# Cover.net
KiCad netlist of a schematic drawn in EAGLE
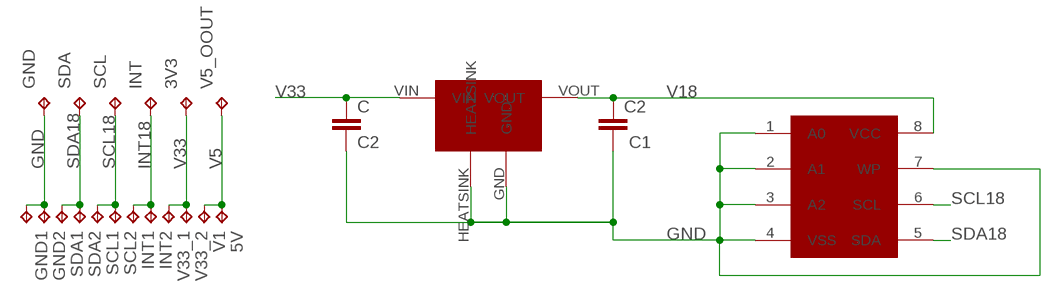
[diagram p0: schematic, sheet 1]

(export (version "E")
  (design (tool "Eeschema 10.0.6"))
  (components
    (comp (ref "3V3")
      (value "TPTP20SQ")
      (footprint "eagle-import:TP20SQ")
      (libsource (lib "eagle-import") (part "TPTP20SQ"))
    )
    (comp (ref "5V")
      (value "V5")
      (footprint "eagle-import:TP20SQ")
      (libsource (lib "eagle-import") (part "TPTP20SQ"))
    )
    (comp (ref "C")
      (value "C2")
      (footprint "eagle-import:C0603")
      (libsource (lib "eagle-import") (part "C-EUC0603"))
    )
    (comp (ref "C2")
      (value "C1")
      (footprint "eagle-import:C0603")
      (libsource (lib "eagle-import") (part "C-EUC0603"))
    )
    (comp (ref "GND")
      (value "TPTP20SQ")
      (footprint "eagle-import:TP20SQ")
      (libsource (lib "eagle-import") (part "TPTP20SQ"))
    )
    (comp (ref "GND1")
      (value "TPTP20SQ")
      (footprint "eagle-import:TP20SQ")
      (libsource (lib "eagle-import") (part "TPTP20SQ"))
    )
    (comp (ref "GND2")
      (value "TPTP20SQ")
      (footprint "eagle-import:TP20SQ")
      (libsource (lib "eagle-import") (part "TPTP20SQ"))
    )
    (comp (ref "INT")
      (value "TPTP20SQ")
      (footprint "eagle-import:TP20SQ")
      (libsource (lib "eagle-import") (part "TPTP20SQ"))
    )
    (comp (ref "INT1")
      (value "TPTP20SQ")
      (footprint "eagle-import:TP20SQ")
      (libsource (lib "eagle-import") (part "TPTP20SQ"))
    )
    (comp (ref "INT2")
      (value "TPTP20SQ")
      (footprint "eagle-import:TP20SQ")
      (libsource (lib "eagle-import") (part "TPTP20SQ"))
    )
    (comp (ref "SCL")
      (value "TPTP20SQ")
      (footprint "eagle-import:TP20SQ")
      (libsource (lib "eagle-import") (part "TPTP20SQ"))
    )
    (comp (ref "SCL1")
      (value "TPTP20SQ")
      (footprint "eagle-import:TP20SQ")
      (libsource (lib "eagle-import") (part "TPTP20SQ"))
    )
    (comp (ref "SCL2")
      (value "TPTP20SQ")
      (footprint "eagle-import:TP20SQ")
      (libsource (lib "eagle-import") (part "TPTP20SQ"))
    )
    (comp (ref "SDA")
      (value "TPTP20SQ")
      (footprint "eagle-import:TP20SQ")
      (libsource (lib "eagle-import") (part "TPTP20SQ"))
    )
    (comp (ref "SDA1")
      (value "SDA")
      (footprint "eagle-import:TP20SQ")
      (libsource (lib "eagle-import") (part "TPTP20SQ"))
    )
    (comp (ref "SDA2")
      (value "SDA")
      (footprint "eagle-import:TP20SQ")
      (libsource (lib "eagle-import") (part "TPTP20SQ"))
    )
    (comp (ref "U$1")
      (value "CAT24")
      (footprint "eagle-import:CAT24")
      (libsource (lib "eagle-import") (part "CAT24"))
    )
    (comp (ref "U$2")
      (value "MCP1700-DFN6")
      (footprint "eagle-import:DFN6-2X2")
      (libsource (lib "eagle-import") (part "MCP1700-DFN6"))
    )
    (comp (ref "V1")
      (value "V5")
      (footprint "eagle-import:TP20SQ")
      (libsource (lib "eagle-import") (part "TPTP20SQ"))
    )
    (comp (ref "V5_OOUT")
      (value "TPTP20SQ")
      (footprint "eagle-import:TP20SQ")
      (libsource (lib "eagle-import") (part "TPTP20SQ"))
    )
    (comp (ref "V33_1")
      (value "TPTP20SQ")
      (footprint "eagle-import:TP20SQ")
      (libsource (lib "eagle-import") (part "TPTP20SQ"))
    )
    (comp (ref "V33_2")
      (value "TPTP20SQ")
      (footprint "eagle-import:TP20SQ")
      (libsource (lib "eagle-import") (part "TPTP20SQ"))
    )
  )
  (nets
    (net (code "1") (name "/GND") (class "Default")
      (node (ref "C") (pin "2") (pinfunction "2_2") (pintype "passive"))
      (node (ref "C2") (pin "2") (pinfunction "2_2") (pintype "passive"))
      (node (ref "GND") (pin "TP") (pinfunction "TP_TP") (pintype "input"))
      (node (ref "GND1") (pin "TP") (pinfunction "TP_TP") (pintype "input"))
      (node (ref "GND2") (pin "TP") (pinfunction "TP_TP") (pintype "input"))
      (node (ref "U$1") (pin "1") (pinfunction "A0_1") (pintype "bidirectional"))
      (node (ref "U$1") (pin "2") (pinfunction "A1_2") (pintype "bidirectional"))
      (node (ref "U$1") (pin "3") (pinfunction "A2_3") (pintype "bidirectional"))
      (node (ref "U$1") (pin "4") (pinfunction "VSS_4") (pintype "bidirectional"))
      (node (ref "U$1") (pin "7") (pinfunction "WP_7") (pintype "bidirectional"))
      (node (ref "U$2") (pin "GND") (pinfunction "GND_GND") (pintype "bidirectional"))
      (node (ref "U$2") (pin "HEATSINK") (pinfunction "HEATSINK_HEATSINK") (pintype "bidirectional"))
    )
    (net (code "2") (name "/INT18") (class "Default")
      (node (ref "INT") (pin "TP") (pinfunction "TP_TP") (pintype "input"))
      (node (ref "INT1") (pin "TP") (pinfunction "TP_TP") (pintype "input"))
      (node (ref "INT2") (pin "TP") (pinfunction "TP_TP") (pintype "input"))
    )
    (net (code "3") (name "/SCL18") (class "Default")
      (node (ref "SCL") (pin "TP") (pinfunction "TP_TP") (pintype "input"))
      (node (ref "SCL1") (pin "TP") (pinfunction "TP_TP") (pintype "input"))
      (node (ref "SCL2") (pin "TP") (pinfunction "TP_TP") (pintype "input"))
      (node (ref "U$1") (pin "6") (pinfunction "SCL_6") (pintype "bidirectional"))
    )
    (net (code "4") (name "/SDA18") (class "Default")
      (node (ref "SDA") (pin "TP") (pinfunction "TP_TP") (pintype "input"))
      (node (ref "SDA1") (pin "TP") (pinfunction "TP_TP") (pintype "input"))
      (node (ref "SDA2") (pin "TP") (pinfunction "TP_TP") (pintype "input"))
      (node (ref "U$1") (pin "5") (pinfunction "SDA_5") (pintype "bidirectional"))
    )
    (net (code "5") (name "/V5") (class "Default")
      (node (ref "5V") (pin "TP") (pinfunction "TP_TP") (pintype "input"))
      (node (ref "V1") (pin "TP") (pinfunction "TP_TP") (pintype "input"))
      (node (ref "V5_OOUT") (pin "TP") (pinfunction "TP_TP") (pintype "input"))
    )
    (net (code "6") (name "/V18") (class "Default")
      (node (ref "C2") (pin "1") (pinfunction "1_1") (pintype "passive"))
      (node (ref "U$1") (pin "8") (pinfunction "VCC_8") (pintype "bidirectional"))
      (node (ref "U$2") (pin "VOUT") (pinfunction "VOUT_VOUT") (pintype "bidirectional"))
    )
    (net (code "7") (name "/V33") (class "Default")
      (node (ref "3V3") (pin "TP") (pinfunction "TP_TP") (pintype "input"))
      (node (ref "C") (pin "1") (pinfunction "1_1") (pintype "passive"))
      (node (ref "U$2") (pin "VIN") (pinfunction "VIN_VIN") (pintype "bidirectional"))
      (node (ref "V33_1") (pin "TP") (pinfunction "TP_TP") (pintype "input"))
      (node (ref "V33_2") (pin "TP") (pinfunction "TP_TP") (pintype "input"))
    )
  )
)
